# Sch_Flyback.net
KiCad netlist of a schematic drawn in Altium Designer
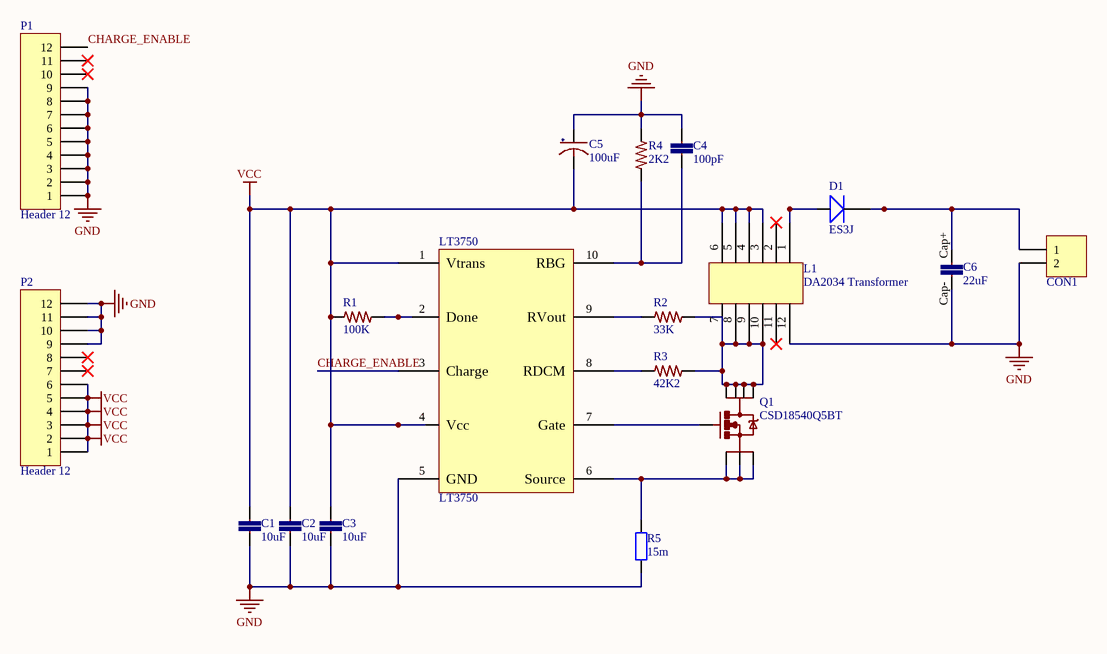
[diagram p0: Sch Flyback.SchDoc]

(export (version "E")
  (design (tool "Eeschema 10.0.6"))
  (components
    (comp (ref "C1")
      (value "10uF")
      (footprint "CAPC0603(1608)55_L")
      (description "CAP CER 10UF 16V X5R 0603")
      (fields (field (name "PART NO") "EMK107BBJ106MA-T"))
      (libsource (lib "IMBEL") (part "CAPACITOR"))
    )
    (comp (ref "C2")
      (value "10uF")
      (footprint "CAPC0603(1608)55_L")
      (description "CAP CER 10UF 16V X5R 0603")
      (fields (field (name "PART NO") "EMK107BBJ106MA-T"))
      (libsource (lib "IMBEL") (part "CAPACITOR"))
    )
    (comp (ref "C3")
      (value "10uF")
      (footprint "CAPC0603(1608)55_L")
      (description "CAP CER 10UF 16V X5R 0603")
      (fields (field (name "PART NO") "EMK107BBJ106MA-T"))
      (libsource (lib "IMBEL") (part "CAPACITOR"))
    )
    (comp (ref "C4")
      (value "100pF")
      (footprint "CAPC0603(1608)55_L")
      (description "CAP CER 100PF 50V NP0 0603")
      (fields (field (name "PART NO") "GRM1885C1H101JA01D"))
      (libsource (lib "IMBEL") (part "CAPACITOR"))
    )
    (comp (ref "C5")
      (value "100uF")
      (footprint "PCBComponent")
      (description "CAP ALUM 100UF 20% 80V SMD")
      (libsource (lib "IMBEL") (part "CAPACITOR-POL"))
    )
    (comp (ref "C6")
      (value "22uF")
      (footprint "CAP ALUM 22UF 250V")
      (libsource (lib "Schlib1") (part "CAP ALUM 22UF 250V"))
    )
    (comp (ref "CON1")
      (value "OSTTA024163")
      (footprint "Term Block 2P")
      (description "2 Position Wire to Board Terminal Block Horizontal with Board 0.200\" (5.08mm) Through Hole")
      (libsource (lib "Schlib1") (part "Term Block 2P"))
    )
    (comp (ref "D1") (value "ES3J") (footprint "Diode") (libsource (lib "Schlib1") (part "Diode")))
    (comp (ref "L1")
      (value "DA2034 Transformer")
      (footprint "DA2034 Transformer")
      (libsource (lib "Schlib1") (part "DA2034 Transformer"))
    )
    (comp (ref "LT3750") (value "LT3750") (footprint "LT3750") (libsource (lib "Schlib1") (part "LT3750")))
    (comp (ref "P1")
      (value "Header 12")
      (footprint "HDR1X12")
      (description "Header, 12-Pin")
      (fields (field (name "PUBLISHER") "Altium Limited"))
      (libsource (lib "Miscellaneous Connectors") (part "Header 12"))
    )
    (comp (ref "P2")
      (value "Header 12")
      (footprint "HDR1X12")
      (description "Header, 12-Pin")
      (fields (field (name "PUBLISHER") "Altium Limited"))
      (libsource (lib "Miscellaneous Connectors") (part "Header 12"))
    )
    (comp (ref "Q1")
      (value "CSD18540Q5BT")
      (footprint "PCBComponent")
      (description "MOSFET N-CH 60V 100A 8VSON")
      (libsource (lib "IMBEL") (part "MOSFET-NCHANNEL"))
    )
    (comp (ref "R1")
      (value "100K")
      (footprint "0402-RES-HD")
      (description "RES 100K OHM 1/10W 1% 0402 SMD 1")
      (fields (field (name "PART NO") "ERJ-2GEJ104X"))
      (libsource (lib "IMBEL") (part "RESISTOR"))
    )
    (comp (ref "R2")
      (value "33K")
      (footprint "0402-RES-HD")
      (description "RES 33K OHM 1/10W 1% 0402 SMD")
      (fields (field (name "PART NO") "ERJ-2RKF3302X"))
      (libsource (lib "IMBEL") (part "RESISTOR"))
    )
    (comp (ref "R3")
      (value "42K2")
      (footprint "0402-RES-HD")
      (description "RES 42.2K OHM 1/10W 1% 0402 SMD")
      (fields (field (name "PART NO") "ERJ-2RKF4222X"))
      (libsource (lib "IMBEL") (part "RESISTOR"))
    )
    (comp (ref "R4")
      (value "2K2")
      (footprint "0402-RES-HD")
      (description "RES 2.2K OHM 1/10W 1% 0402 SMD")
      (fields (field (name "PART NO") "ERJ-2RKF2201X"))
      (libsource (lib "IMBEL") (part "RESISTOR"))
    )
    (comp (ref "R5")
      (value "15m")
      (footprint "RES1206")
      (description "Current Sense Resistors - SMD 1206 1Watt 0.015Ohms 1%")
      (fields (field (name "PUBLISHER") "Altium Limited"))
      (libsource (lib "Schlib1") (part "Res2"))
    )
  )
  (nets
    (net (code "1") (name "/CHARGE_ENABLE") (class "Default")
      (node (ref "LT3750") (pin "3") (pinfunction "Charge_3") (pintype "passive"))
      (node (ref "P1") (pin "12") (pinfunction "12_12") (pintype "passive"))
    )
    (net (code "2") (name "GND") (class "Default")
      (node (ref "C1") (pin "2") (pinfunction "2_2") (pintype "passive"))
      (node (ref "C2") (pin "2") (pinfunction "2_2") (pintype "passive"))
      (node (ref "C3") (pin "2") (pinfunction "2_2") (pintype "passive"))
      (node (ref "C4") (pin "1") (pinfunction "1_1") (pintype "passive"))
      (node (ref "C5") (pin "1") (pinfunction "+_1") (pintype "passive"))
      (node (ref "C6") (pin "Cap-") (pinfunction "Cap-_Cap-") (pintype "passive"))
      (node (ref "CON1") (pin "2") (pinfunction "2_2") (pintype "passive"))
      (node (ref "L1") (pin "12") (pinfunction "12_12") (pintype "passive"))
      (node (ref "LT3750") (pin "5") (pinfunction "GND_5") (pintype "passive"))
      (node (ref "P1") (pin "1") (pinfunction "1_1") (pintype "passive"))
      (node (ref "P1") (pin "2") (pinfunction "2_2") (pintype "passive"))
      (node (ref "P1") (pin "3") (pinfunction "3_3") (pintype "passive"))
      (node (ref "P1") (pin "4") (pinfunction "4_4") (pintype "passive"))
      (node (ref "P1") (pin "5") (pinfunction "5_5") (pintype "passive"))
      (node (ref "P1") (pin "6") (pinfunction "6_6") (pintype "passive"))
      (node (ref "P1") (pin "7") (pinfunction "7_7") (pintype "passive"))
      (node (ref "P1") (pin "8") (pinfunction "8_8") (pintype "passive"))
      (node (ref "P1") (pin "9") (pinfunction "9_9") (pintype "passive"))
      (node (ref "P2") (pin "10") (pinfunction "10_10") (pintype "passive"))
      (node (ref "P2") (pin "11") (pinfunction "11_11") (pintype "passive"))
      (node (ref "P2") (pin "12") (pinfunction "12_12") (pintype "passive"))
      (node (ref "P2") (pin "9") (pinfunction "9_9") (pintype "passive"))
      (node (ref "R4") (pin "2") (pinfunction "2_2") (pintype "passive"))
      (node (ref "R5") (pin "2") (pinfunction "2_2") (pintype "passive"))
    )
    (net (code "3") (name "Net-(C6-PadCap+)") (class "Default")
      (node (ref "C6") (pin "Cap+") (pinfunction "Cap+_Cap+") (pintype "passive"))
      (node (ref "CON1") (pin "1") (pinfunction "1_1") (pintype "passive"))
      (node (ref "D1") (pin "D1+") (pinfunction "D1+_D1+") (pintype "passive"))
    )
    (net (code "4") (name "Net-(D1-PadD1-)") (class "Default")
      (node (ref "D1") (pin "D1-") (pinfunction "D1-_D1-") (pintype "passive"))
      (node (ref "L1") (pin "1") (pinfunction "1_1") (pintype "passive"))
    )
    (net (code "5") (name "Net-(L1-Pad10)") (class "Default")
      (node (ref "L1") (pin "10") (pinfunction "10_10") (pintype "passive"))
      (node (ref "L1") (pin "7") (pinfunction "7_7") (pintype "passive"))
      (node (ref "L1") (pin "8") (pinfunction "8_8") (pintype "passive"))
      (node (ref "L1") (pin "9") (pinfunction "9_9") (pintype "passive"))
      (node (ref "Q1") (pin "5") (pinfunction "D_5") (pintype "passive"))
      (node (ref "Q1") (pin "6") (pinfunction "D_6") (pintype "passive"))
      (node (ref "Q1") (pin "7") (pinfunction "D_7") (pintype "passive"))
      (node (ref "Q1") (pin "8") (pinfunction "D_8") (pintype "passive"))
      (node (ref "R2") (pin "2") (pinfunction "2_2") (pintype "passive"))
      (node (ref "R3") (pin "1") (pinfunction "1_1") (pintype "passive"))
    )
    (net (code "6") (name "Net-(LT3750-Done)") (class "Default")
      (node (ref "LT3750") (pin "2") (pinfunction "Done_2") (pintype "passive"))
      (node (ref "R1") (pin "2") (pinfunction "2_2") (pintype "passive"))
    )
    (net (code "7") (name "Net-(LT3750-Gate)") (class "Default")
      (node (ref "LT3750") (pin "7") (pinfunction "Gate_7") (pintype "passive"))
      (node (ref "Q1") (pin "4") (pinfunction "G_4") (pintype "passive"))
    )
    (net (code "8") (name "Net-(LT3750-RBG)") (class "Default")
      (node (ref "C4") (pin "2") (pinfunction "2_2") (pintype "passive"))
      (node (ref "LT3750") (pin "10") (pinfunction "RBG_10") (pintype "passive"))
      (node (ref "R4") (pin "1") (pinfunction "1_1") (pintype "passive"))
    )
    (net (code "9") (name "Net-(LT3750-RDCM)") (class "Default")
      (node (ref "LT3750") (pin "8") (pinfunction "RDCM_8") (pintype "passive"))
      (node (ref "R3") (pin "2") (pinfunction "2_2") (pintype "passive"))
    )
    (net (code "10") (name "Net-(LT3750-RVout)") (class "Default")
      (node (ref "LT3750") (pin "9") (pinfunction "RVout_9") (pintype "passive"))
      (node (ref "R2") (pin "1") (pinfunction "1_1") (pintype "passive"))
    )
    (net (code "11") (name "Net-(LT3750-Source)") (class "Default")
      (node (ref "LT3750") (pin "6") (pinfunction "Source_6") (pintype "passive"))
      (node (ref "Q1") (pin "1") (pinfunction "S_1") (pintype "passive"))
      (node (ref "Q1") (pin "2") (pinfunction "S_2") (pintype "passive"))
      (node (ref "Q1") (pin "3") (pinfunction "S_3") (pintype "passive"))
      (node (ref "R5") (pin "1") (pinfunction "1_1") (pintype "passive"))
    )
    (net (code "12") (name "VCC") (class "Default")
      (node (ref "C1") (pin "1") (pinfunction "1_1") (pintype "passive"))
      (node (ref "C2") (pin "1") (pinfunction "1_1") (pintype "passive"))
      (node (ref "C3") (pin "1") (pinfunction "1_1") (pintype "passive"))
      (node (ref "C5") (pin "2") (pinfunction "-_2") (pintype "passive"))
      (node (ref "L1") (pin "3") (pinfunction "3_3") (pintype "passive"))
      (node (ref "L1") (pin "4") (pinfunction "4_4") (pintype "passive"))
      (node (ref "L1") (pin "5") (pinfunction "5_5") (pintype "passive"))
      (node (ref "L1") (pin "6") (pinfunction "6_6") (pintype "passive"))
      (node (ref "LT3750") (pin "1") (pinfunction "Vtrans_1") (pintype "passive"))
      (node (ref "LT3750") (pin "4") (pinfunction "Vcc_4") (pintype "passive"))
      (node (ref "P2") (pin "1") (pinfunction "1_1") (pintype "passive"))
      (node (ref "P2") (pin "2") (pinfunction "2_2") (pintype "passive"))
      (node (ref "P2") (pin "3") (pinfunction "3_3") (pintype "passive"))
      (node (ref "P2") (pin "4") (pinfunction "4_4") (pintype "passive"))
      (node (ref "P2") (pin "5") (pinfunction "5_5") (pintype "passive"))
      (node (ref "P2") (pin "6") (pinfunction "6_6") (pintype "passive"))
      (node (ref "R1") (pin "1") (pinfunction "1_1") (pintype "passive"))
    )
    (net (code "13") (name "unconnected-(L1-Pad2)") (class "Default")
      (node (ref "L1") (pin "2") (pinfunction "2_2") (pintype "passive+no_connect"))
    )
    (net (code "14") (name "unconnected-(L1-Pad11)") (class "Default")
      (node (ref "L1") (pin "11") (pinfunction "11_11") (pintype "passive+no_connect"))
    )
    (net (code "15") (name "unconnected-(P1-Pad10)") (class "Default")
      (node (ref "P1") (pin "10") (pinfunction "10_10") (pintype "passive+no_connect"))
    )
    (net (code "16") (name "unconnected-(P1-Pad11)") (class "Default")
      (node (ref "P1") (pin "11") (pinfunction "11_11") (pintype "passive+no_connect"))
    )
    (net (code "17") (name "unconnected-(P2-Pad7)") (class "Default")
      (node (ref "P2") (pin "7") (pinfunction "7_7") (pintype "passive+no_connect"))
    )
    (net (code "18") (name "unconnected-(P2-Pad8)") (class "Default")
      (node (ref "P2") (pin "8") (pinfunction "8_8") (pintype "passive+no_connect"))
    )
  )
)
